# Sensores2.net
KiCad netlist of a schematic drawn in Altium Designer
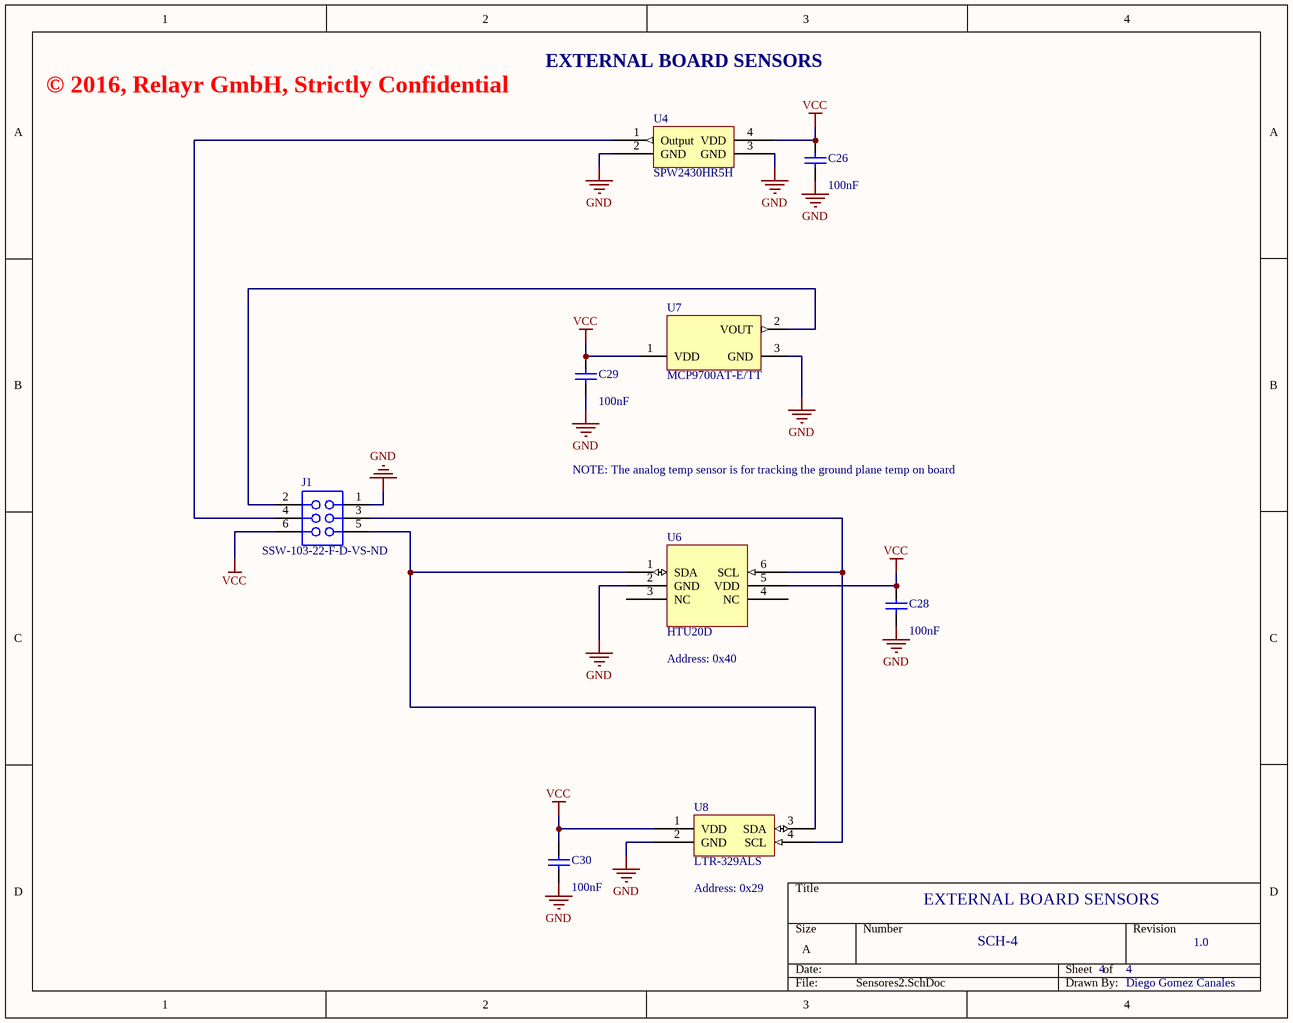
[diagram p0: Sensores2.SchDoc]

(export (version "E")
  (design (tool "Eeschema 10.0.6"))
  (components
    (comp (ref "C26")
      (value "100nF")
      (footprint "6-0805_N")
      (description "Capacitor")
      (fields (field (name "Comment") "Cap") (field (name "PUBLISHER") "Altium Limited"))
      (libsource (lib "Miscellaneous Devices") (part "Cap"))
    )
    (comp (ref "C28")
      (value "100nF")
      (footprint "6-0805_N")
      (description "Capacitor")
      (fields (field (name "Comment") "Cap") (field (name "PUBLISHER") "Altium Limited"))
      (libsource (lib "Miscellaneous Devices") (part "Cap"))
    )
    (comp (ref "C29")
      (value "100nF")
      (footprint "6-0805_N")
      (description "Capacitor")
      (fields (field (name "Comment") "Cap") (field (name "PUBLISHER") "Altium Limited"))
      (libsource (lib "Miscellaneous Devices") (part "Cap"))
    )
    (comp (ref "C30")
      (value "100nF")
      (footprint "6-0805_N")
      (description "Capacitor")
      (fields (field (name "Comment") "Cap") (field (name "PUBLISHER") "Altium Limited"))
      (libsource (lib "Miscellaneous Devices") (part "Cap"))
    )
    (comp (ref "J1")
      (value "SMTC-SSW-103-01-X-D")
      (footprint "SMTC-SSW-103-22-X-S-VS")
      (fields (field (name "SUPPLIER PART NUMBER 1") "SSW-103-22-F-D-VS-ND"))
      (libsource (lib "Pasive_components") (part "SMTC-SSW-103-01-X-D"))
    )
    (comp (ref "U4")
      (value "SPW2430HR5H")
      (footprint "DFN3127P600-8N")
      (description "Knowles MEMS Microphone")
      (libsource (lib "SPW2430HR5H_Microphone") (part "SPW2430HR5H"))
    )
    (comp (ref "U6")
      (value "HTU20D")
      (footprint "HTU20D_DFN6")
      (description "Digital relative Humidity sensor with temperature output")
      (libsource (lib "HTU20D_TempHum") (part "HTU20D"))
    )
    (comp (ref "U7")
      (value "MCP9700AT-E/TT")
      (footprint "SOT-23-TT3_L")
      (description "Low-Power Linear Active Thermistor IC, 3-Pin SOT-23, Extended Temperature, Tape and Reel")
      (libsource (lib "Altium Content Vault") (part "CMP-0192-00218-1"))
    )
    (comp (ref "U8")
      (value "LTR-329ALS")
      (footprint "ChipLED4Pin2X2X07")
      (description "Digital Ambient Light Sensor")
      (libsource (lib "LTR-329ALS_AmbientLight") (part "LTR-329ALS"))
    )
  )
  (nets
    (net (code "1") (name "GND") (class "Default")
      (node (ref "C26") (pin "1") (pinfunction "1_1") (pintype "passive"))
      (node (ref "C28") (pin "1") (pinfunction "1_1") (pintype "passive"))
      (node (ref "C29") (pin "1") (pinfunction "1_1") (pintype "passive"))
      (node (ref "C30") (pin "1") (pinfunction "1_1") (pintype "passive"))
      (node (ref "J1") (pin "1") (pinfunction "1_1") (pintype "passive"))
      (node (ref "U4") (pin "2") (pinfunction "GND_2") (pintype "power_in"))
      (node (ref "U4") (pin "3") (pinfunction "GND_3") (pintype "power_in"))
      (node (ref "U6") (pin "2") (pinfunction "GND_2") (pintype "power_in"))
      (node (ref "U7") (pin "3") (pinfunction "GND_3") (pintype "power_in"))
      (node (ref "U8") (pin "2") (pinfunction "GND_2") (pintype "power_in"))
    )
    (net (code "2") (name "Net-(U4-Output)") (class "Default")
      (node (ref "J1") (pin "4") (pinfunction "4_4") (pintype "passive"))
      (node (ref "U4") (pin "1") (pinfunction "Output_1") (pintype "output"))
    )
    (net (code "3") (name "Net-(U6-SCL)") (class "Default")
      (node (ref "J1") (pin "3") (pinfunction "3_3") (pintype "passive"))
      (node (ref "U6") (pin "6") (pinfunction "SCL_6") (pintype "input"))
      (node (ref "U8") (pin "4") (pinfunction "SCL_4") (pintype "input"))
    )
    (net (code "4") (name "Net-(U6-SDA)") (class "Default")
      (node (ref "J1") (pin "5") (pinfunction "5_5") (pintype "passive"))
      (node (ref "U6") (pin "1") (pinfunction "SDA_1") (pintype "bidirectional"))
      (node (ref "U8") (pin "3") (pinfunction "SDA_3") (pintype "bidirectional"))
    )
    (net (code "5") (name "Net-(U7-VOUT)") (class "Default")
      (node (ref "J1") (pin "2") (pinfunction "2_2") (pintype "passive"))
      (node (ref "U7") (pin "2") (pinfunction "VOUT_2") (pintype "output"))
    )
    (net (code "6") (name "VCC") (class "Default")
      (node (ref "C26") (pin "2") (pinfunction "2_2") (pintype "passive"))
      (node (ref "C28") (pin "2") (pinfunction "2_2") (pintype "passive"))
      (node (ref "C29") (pin "2") (pinfunction "2_2") (pintype "passive"))
      (node (ref "C30") (pin "2") (pinfunction "2_2") (pintype "passive"))
      (node (ref "J1") (pin "6") (pinfunction "6_6") (pintype "passive"))
      (node (ref "U4") (pin "4") (pinfunction "VDD_4") (pintype "power_in"))
      (node (ref "U6") (pin "5") (pinfunction "VDD_5") (pintype "power_in"))
      (node (ref "U7") (pin "1") (pinfunction "VDD_1") (pintype "power_in"))
      (node (ref "U8") (pin "1") (pinfunction "VDD_1") (pintype "power_in"))
    )
    (net (code "7") (name "unconnected-(U6-NC-Pad3)") (class "Default")
      (node (ref "U6") (pin "3") (pinfunction "NC_3") (pintype "passive"))
    )
    (net (code "8") (name "unconnected-(U6-NC-Pad4)") (class "Default")
      (node (ref "U6") (pin "4") (pinfunction "NC_4") (pintype "passive"))
    )
  )
)
